# Main.net
KiCad netlist of a schematic drawn in Altium Designer
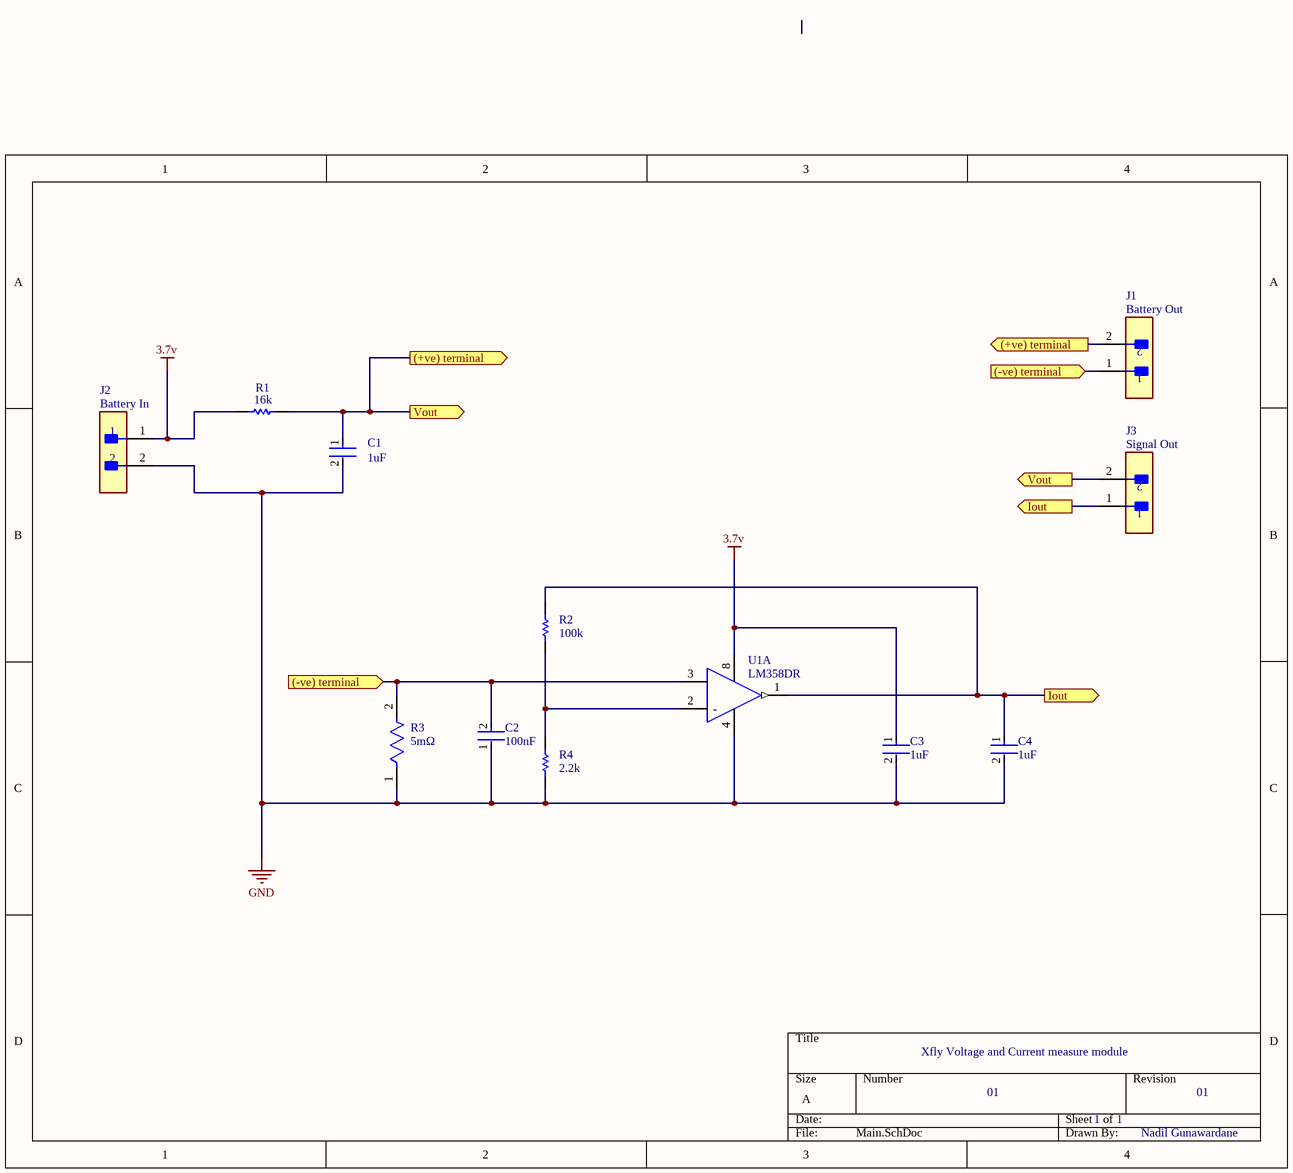
[diagram p0: Main.SchDoc]

(export (version "E")
  (design (tool "Eeschema 10.0.6"))
  (components
    (comp (ref "C1")
      (value "CL21F105ZAFNNNF")
      (footprint "FP-CL21-IPC_B")
      (description "CL21 Series 0805 1uF 25V -20/+80% Tolerance Y5V Multilayer Ceramic Chip Capacitor")
      (fields (field (name "CAPACITANCE") "1uF") (field (name "TOLERANCE") "80%"))
      (libsource (lib "Altium Content Vault") (part "b4654b650e69147ec39a6b967a45e02"))
    )
    (comp (ref "C2")
      (value "GCJ188R71H104KA12D")
      (footprint "FP-GCJ188-0_2-MFG")
      (description "Cap Ceramic 0.1uF 50V X7R 10% Pad SMD 0603 Soft Termination +125°C Automotive T/R")
      (fields (field (name "TOLERANCE") "10%") (field (name "CAPACITANCE") "100nF"))
      (libsource (lib "Altium Content Vault") (part "f23184f103b6ebe33a8c269c53dcba6"))
    )
    (comp (ref "C3")
      (value "CL21F105ZAFNNNF")
      (footprint "FP-CL21-IPC_B")
      (description "CL21 Series 0805 1uF 25V -20/+80% Tolerance Y5V Multilayer Ceramic Chip Capacitor")
      (fields (field (name "CAPACITANCE") "1uF") (field (name "TOLERANCE") "80%"))
      (libsource (lib "Altium Content Vault") (part "b4654b650e69147ec39a6b967a45e02"))
    )
    (comp (ref "C4")
      (value "CL21F105ZAFNNNF")
      (footprint "FP-CL21-IPC_B")
      (description "CL21 Series 0805 1uF 25V -20/+80% Tolerance Y5V Multilayer Ceramic Chip Capacitor")
      (fields (field (name "CAPACITANCE") "1uF") (field (name "TOLERANCE") "80%"))
      (libsource (lib "Altium Content Vault") (part "b4654b650e69147ec39a6b967a45e02"))
    )
    (comp (ref "J1")
      (value "Battery Out")
      (footprint "FP-26-48-1025-MFG")
      (description "CONN HEADER VERT 2POS 3.96MM")
      (libsource (lib "Altium Content Vault") (part "3bc925449376181038e59eaffc5286c"))
    )
    (comp (ref "J2")
      (value "Battery In")
      (footprint "FP-26-48-1025-MFG")
      (description "CONN HEADER VERT 2POS 3.96MM")
      (libsource (lib "") (part "3bc925449376181038e59eaffc5286c_1"))
    )
    (comp (ref "J3")
      (value "Signal Out")
      (footprint "FP-26-48-1025-MFG")
      (description "CONN HEADER VERT 2POS 3.96MM")
      (libsource (lib "Altium Content Vault") (part "3bc925449376181038e59eaffc5286c"))
    )
    (comp (ref "R1")
      (value "16k")
      (footprint "RESC1608X55X30ML15T15")
      (fields (field (name "MANUFACTURER") "Panasonic") (field (name "PART NUMBER") "ERJ-3EKF1602V"))
      (libsource (lib "Altium Content Vault") (part "RES"))
    )
    (comp (ref "R2")
      (value "100k")
      (footprint "RESC1005X37X25ML05T10")
      (fields (field (name "PART NUMBER") "RE0402DR-07100KL") (field (name "MANUFACTURER") "Yageo / Phycomp"))
      (libsource (lib "Altium Content Vault") (part "RES"))
    )
    (comp (ref "R3")
      (value "5mΩ")
      (footprint "FP-PA2512E-0R005-0R006-MFG")
      (description "METAL CURRENT SENSOR 2512 1% 50P")
      (fields (field (name "MANUFACTURER") "Yageo") (field (name "TOLERANCE") "1%"))
      (libsource (lib "Altium Content Vault") (part "1029c3af85768c4190bb7ad29bc67b5"))
    )
    (comp (ref "R4")
      (value "2.2k")
      (footprint "RESC1609X50X30LL10T20")
      (fields (field (name "MANUFACTURER") "Vishay Dale") (field (name "PART NUMBER") "CRCW06032K20JNEA"))
      (libsource (lib "Altium Content Vault") (part "RES"))
    )
    (comp (ref "U1")
      (value "LM358DR")
      (footprint "FP-D0008A-MFG")
      (description "IC OPAMP GP 2 CIRCUIT 8SOIC")
      (libsource (lib "Altium Content Vault") (part "0afdfe5f461d2cdd85604ff8654be97"))
    )
  )
  (nets
    (net (code "1") (name "/(+ve) terminal") (class "Default")
      (node (ref "C1") (pin "1") (pinfunction "1_1") (pintype "passive"))
      (node (ref "J1") (pin "2") (pinfunction "2_2") (pintype "passive"))
      (node (ref "J3") (pin "2") (pinfunction "2_2") (pintype "passive"))
      (node (ref "R1") (pin "2") (pinfunction "2_2") (pintype "passive"))
    )
    (net (code "2") (name "/(-ve) terminal") (class "Default")
      (node (ref "C2") (pin "2") (pinfunction "2_2") (pintype "passive"))
      (node (ref "J1") (pin "1") (pinfunction "1_1") (pintype "passive"))
      (node (ref "R3") (pin "2") (pinfunction "2_2") (pintype "passive"))
      (node (ref "U1") (pin "3") (pinfunction "IN1+_3") (pintype "tri_state"))
    )
    (net (code "3") (name "/Iout") (class "Default")
      (node (ref "C4") (pin "1") (pinfunction "1_1") (pintype "passive"))
      (node (ref "J3") (pin "1") (pinfunction "1_1") (pintype "passive"))
      (node (ref "R2") (pin "2") (pinfunction "2_2") (pintype "passive"))
      (node (ref "U1") (pin "1") (pinfunction "1OUT_1") (pintype "output"))
    )
    (net (code "4") (name "3.7v") (class "Default")
      (node (ref "C3") (pin "1") (pinfunction "1_1") (pintype "passive"))
      (node (ref "J2") (pin "1") (pinfunction "1_1") (pintype "passive"))
      (node (ref "R1") (pin "1") (pinfunction "1_1") (pintype "passive"))
      (node (ref "U1") (pin "8") (pinfunction "V+_8") (pintype "power_in"))
    )
    (net (code "5") (name "GND") (class "Default")
      (node (ref "C1") (pin "2") (pinfunction "2_2") (pintype "passive"))
      (node (ref "C2") (pin "1") (pinfunction "1_1") (pintype "passive"))
      (node (ref "C3") (pin "2") (pinfunction "2_2") (pintype "passive"))
      (node (ref "C4") (pin "2") (pinfunction "2_2") (pintype "passive"))
      (node (ref "J2") (pin "2") (pinfunction "2_2") (pintype "passive"))
      (node (ref "R3") (pin "1") (pinfunction "1_1") (pintype "passive"))
      (node (ref "R4") (pin "1") (pinfunction "1_1") (pintype "passive"))
      (node (ref "U1") (pin "4") (pinfunction "V-_4") (pintype "power_in"))
    )
    (net (code "6") (name "Net-(U1A-IN1-)") (class "Default")
      (node (ref "R2") (pin "1") (pinfunction "1_1") (pintype "passive"))
      (node (ref "R4") (pin "2") (pinfunction "2_2") (pintype "passive"))
      (node (ref "U1") (pin "2") (pinfunction "IN1-_2") (pintype "tri_state"))
    )
  )
)
